# Stepper-Driver.net
KiCad netlist of a schematic drawn in Altium Designer
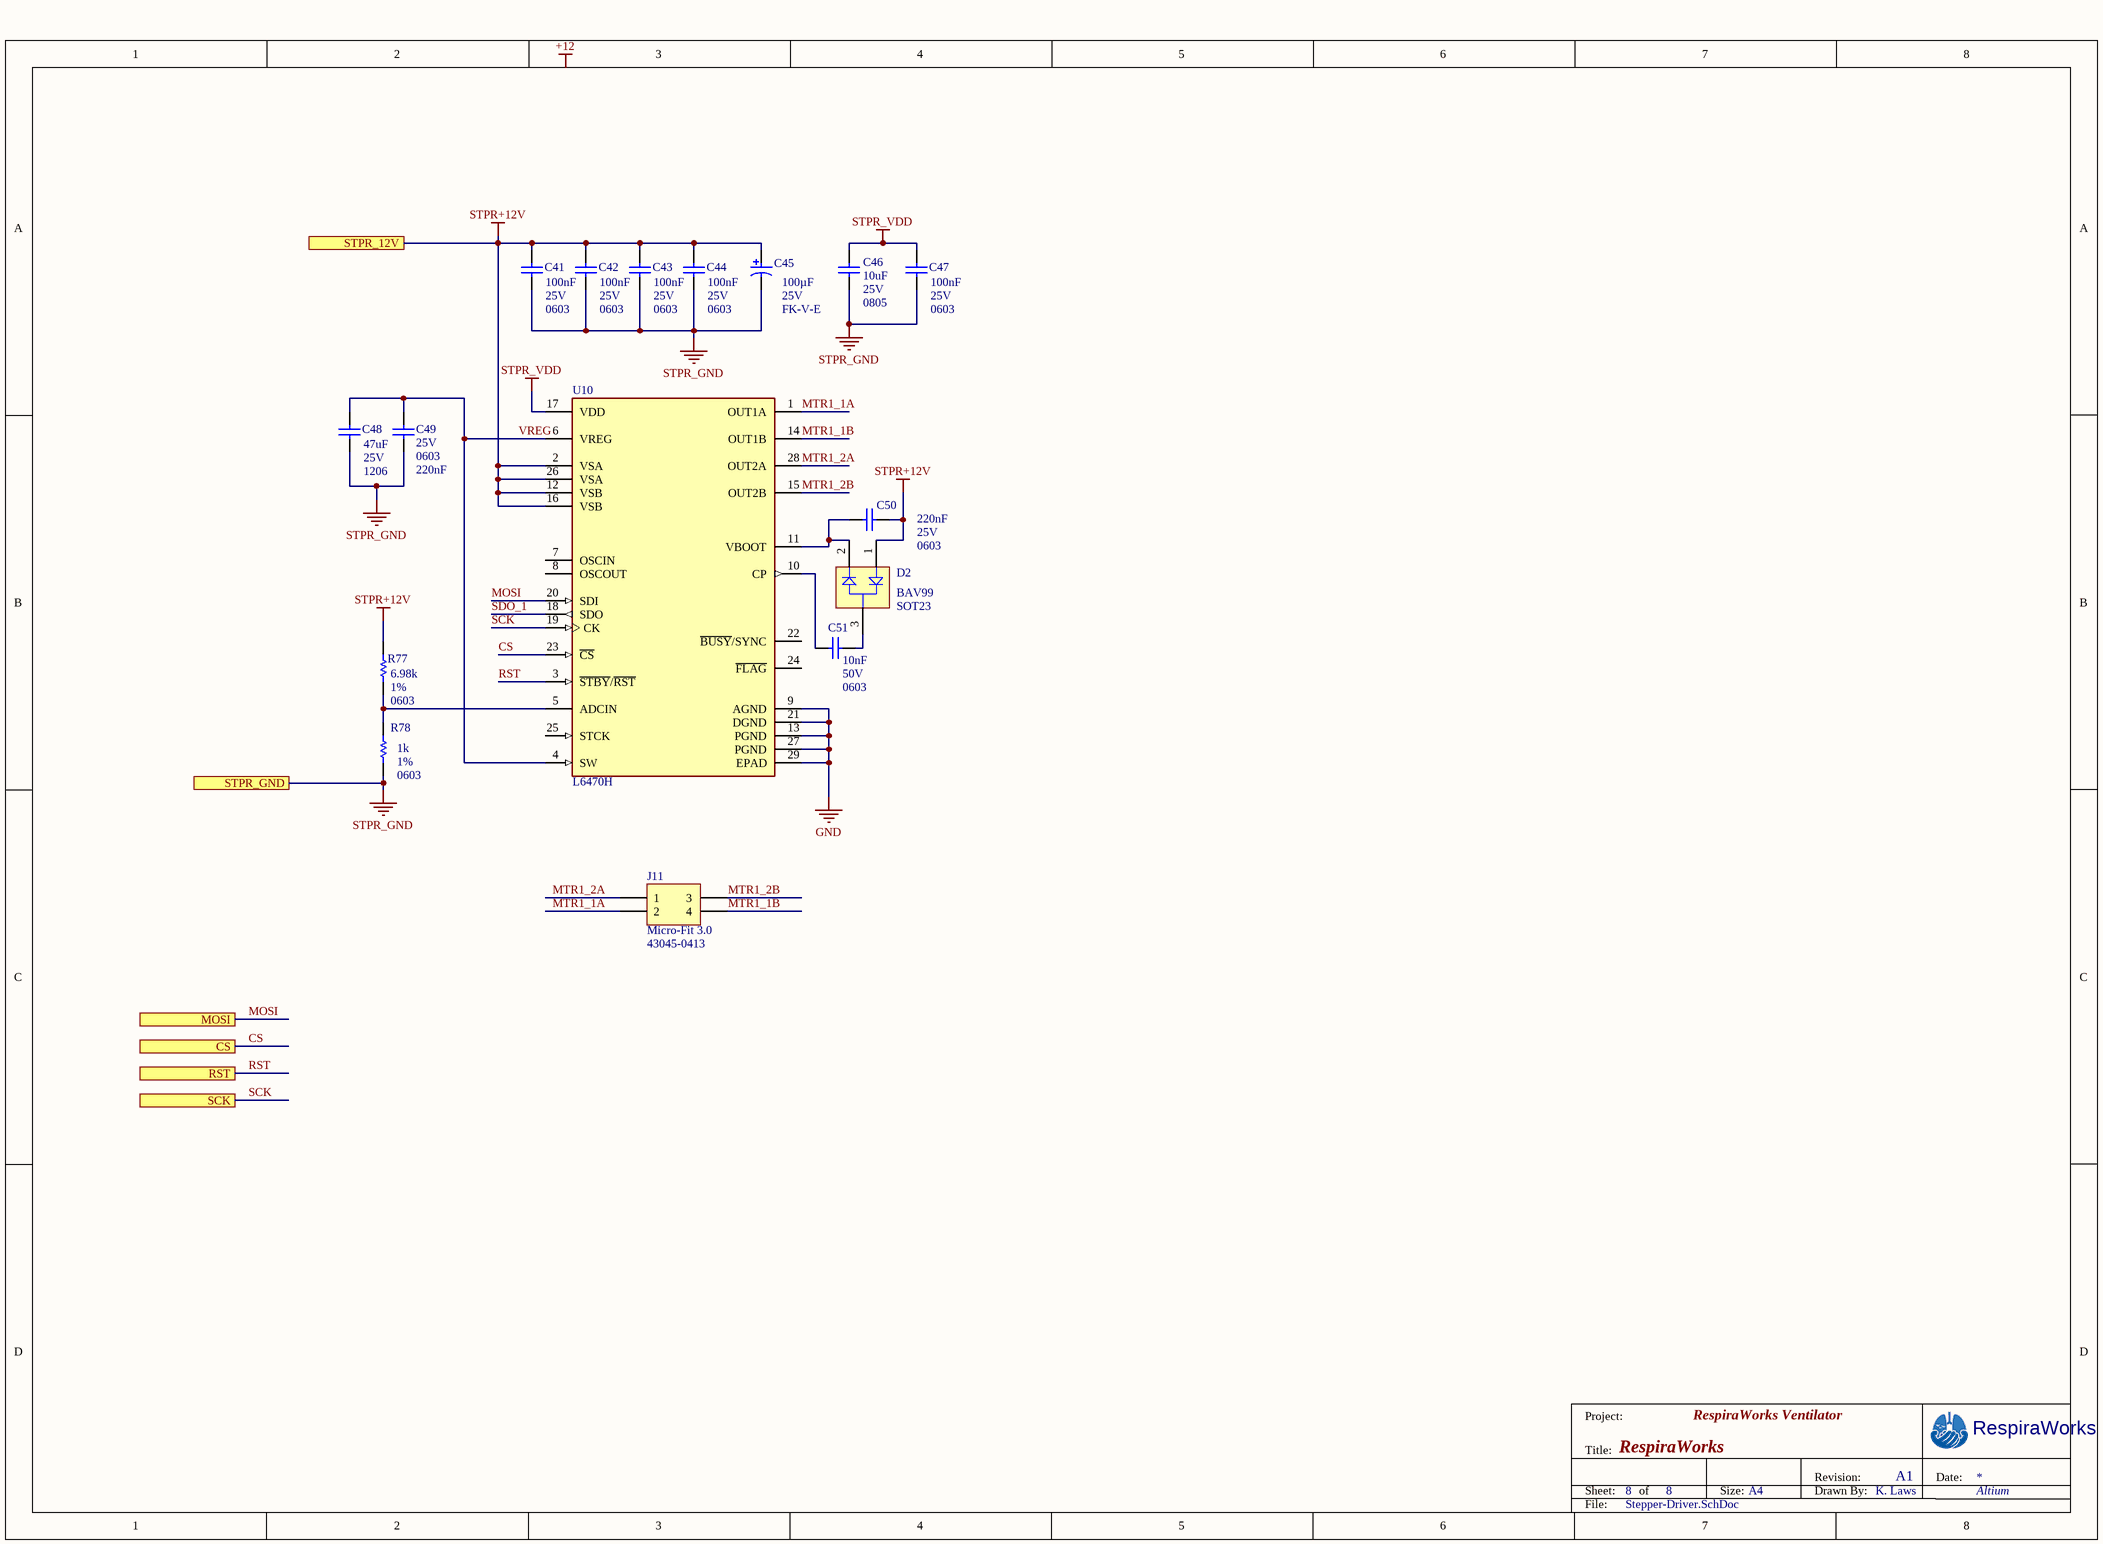
[diagram p0: Stepper-Driver.SchDoc]

(export (version "E")
  (design (tool "Eeschema 10.0.6"))
  (components
    (comp (ref "C41")
      (value "C0603C104Z3VACTU")
      (footprint "pcbreath:CAPC1608X87X35NL15T15")
      (fields
        (field (name "MANUFACTURER") "Kemet")
        (field (name "CASE/PACKAGE") "0603")
        (field (name "CAPACITANCE") "100nF")
        (field (name "TOLERANCE") "80%")
        (field (name "VOLTAGE RATING") "25V")
        (field (name "VOLTAGE") "25V")
      )
      (libsource (lib "pcbreath") (part "Capacitor 220nF"))
    )
    (comp (ref "C42")
      (value "C0603C104Z3VACTU")
      (footprint "pcbreath:CAPC1608X87X35NL15T15")
      (fields
        (field (name "MANUFACTURER") "Kemet")
        (field (name "CASE/PACKAGE") "0603")
        (field (name "CAPACITANCE") "100nF")
        (field (name "TOLERANCE") "80%")
        (field (name "VOLTAGE RATING") "25V")
        (field (name "VOLTAGE") "25V")
      )
      (libsource (lib "pcbreath") (part "Capacitor 220nF"))
    )
    (comp (ref "C43")
      (value "C0603C104Z3VACTU")
      (footprint "pcbreath:CAPC1608X87X35NL15T15")
      (fields
        (field (name "MANUFACTURER") "Kemet")
        (field (name "CASE/PACKAGE") "0603")
        (field (name "CAPACITANCE") "100nF")
        (field (name "TOLERANCE") "80%")
        (field (name "VOLTAGE RATING") "25V")
        (field (name "VOLTAGE") "25V")
      )
      (libsource (lib "pcbreath") (part "Capacitor 220nF"))
    )
    (comp (ref "C44")
      (value "C0603C104Z3VACTU")
      (footprint "pcbreath:CAPC1608X87X35NL15T15")
      (fields
        (field (name "MANUFACTURER") "Kemet")
        (field (name "CASE/PACKAGE") "0603")
        (field (name "CAPACITANCE") "100nF")
        (field (name "TOLERANCE") "80%")
        (field (name "VOLTAGE RATING") "25V")
        (field (name "VOLTAGE") "25V")
      )
      (libsource (lib "pcbreath") (part "Capacitor 220nF"))
    )
    (comp (ref "C45")
      (value "EEEFK1E101P")
      (footprint "pcbreath:PNSC-FK-V-E_V")
      (fields
        (field (name "RATED VOLTAGE") "25V")
        (field (name "PACKAGE REFERENCE") "FK-V-E")
        (field (name "MANUFACTURER") "Panasonic")
        (field (name "CAPACITANCE") "100µF")
      )
      (libsource (lib "pcbreath") (part "Capacitor 100 uF"))
    )
    (comp (ref "C46")
      (value "Capacitor 10 uF")
      (footprint "pcbreath:CAPC2013X135X45LL10T25")
      (description "Generic capacitor 0805 pkg")
      (fields
        (field (name "TOLERANCE") "10%")
        (field (name "VOLTAGE") "25V")
        (field (name "VOLTAGE RATING") "25V")
        (field (name "CASE/PACKAGE") "0805")
        (field (name "CAPACITANCE") "10uF")
      )
      (libsource (lib "pcbreath") (part "Capacitor 10 uF"))
    )
    (comp (ref "C47")
      (value "C0603C104Z3VACTU")
      (footprint "pcbreath:CAPC1608X87X35NL15T15")
      (fields
        (field (name "MANUFACTURER") "Kemet")
        (field (name "CASE/PACKAGE") "0603")
        (field (name "CAPACITANCE") "100nF")
        (field (name "TOLERANCE") "80%")
        (field (name "VOLTAGE RATING") "25V")
        (field (name "VOLTAGE") "25V")
      )
      (libsource (lib "pcbreath") (part "Capacitor 220nF"))
    )
    (comp (ref "C48")
      (value "Capacitor 47uF")
      (footprint "pcbreath:FP-C3216-160-IPC_B")
      (fields
        (field (name "CASE/PACKAGE") "1206")
        (field (name "CAPACITANCE") "47uF")
        (field (name "TOLERANCE") "20%")
        (field (name "VOLTAGE RATING") "25V")
        (field (name "VOLTAGE") "25V")
      )
      (libsource (lib "pcbreath") (part "Capacitor 47uF"))
    )
    (comp (ref "C49")
      (value "Capacitor 220nF")
      (footprint "pcbreath:CAPC1608X87X35NL15T15")
      (description "Capacitor 220 nF 25 VDC PU=4000 ST, GRM188R71E224KA88D, Murata")
      (fields
        (field (name "TOLERANCE") "10%")
        (field (name "VOLTAGE") "50V")
        (field (name "VOLTAGE RATING (DC)") "25V")
        (field (name "CASE/PACKAGE") "0603")
        (field (name "CAPACITANCE") "220nF")
      )
      (libsource (lib "") (part "Capacitor 220nF_1"))
    )
    (comp (ref "C50")
      (value "Capacitor 220nF")
      (footprint "CAPC0603(1608)100_L")
      (description "Capacitor 220 nF 25 VDC PU=4000 ST, GRM188R71E224KA88D, Murata")
      (fields
        (field (name "TOLERANCE") "10%")
        (field (name "VOLTAGE") "50V")
        (field (name "VOLTAGE RATING (DC)") "25V")
        (field (name "CASE/PACKAGE") "0603")
        (field (name "CAPACITANCE") "220nF")
      )
      (libsource (lib "") (part "Capacitor 220nF_1"))
    )
    (comp (ref "C51")
      (value "Capacitor 10nF")
      (footprint "pcbreath:CAPC0603(1608)100_L")
      (description "Cap Ceramic 0.01uF 50V X7R 10% SMD 0603 125C Automotive T/R")
      (fields
        (field (name "TOLERANCE") "10%")
        (field (name "VOLTAGE") "50V")
        (field (name "VOLTAGE RATING (DC)") "50V")
        (field (name "CAPACITANCE") "10nF")
        (field (name "CASE/PACKAGE") "0603")
      )
      (libsource (lib "pcbreath") (part "Capacitor 10nF"))
    )
    (comp (ref "D2")
      (value "BAV99")
      (footprint "pcbreath:INF-SOT23_L")
      (description "Silicon Switching Diode, SOT23, Reel, Green")
      (fields (field (name "MANUFACTURER") "Infineon") (field (name "PACKAGEREFERENCE") "SOT23"))
      (libsource (lib "pcbreath") (part "Silicon Switching Diode"))
    )
    (comp (ref "J11")
      (value "Micro-Fit 3.0")
      (footprint "pcbreath:43045-0413")
      (description "Conn, Micro-Fit 3.0, PCB Male Pin, 2x2pos, Thru-hole")
      (fields (field (name "MANUFACTURER") "Molex") (field (name "MANUFACTURER P/N") "43045-0413"))
      (libsource (lib "pcbreath") (part "43045-0413"))
    )
    (comp (ref "R77")
      (value "Res 6.98k")
      (footprint "pcbreath:RESC1608X55X30NL15T15")
      (fields
        (field (name "TOLERANCE") "1%")
        (field (name "CASE/PACKAGE") "0603")
        (field (name "RESISTANCE") "6.98k")
      )
      (libsource (lib "pcbreath") (part "Res 6.98k"))
    )
    (comp (ref "R78")
      (value "Res 1.0k 0603")
      (footprint "pcbreath:RESC1608X55X30NL15T15")
      (description "Res Thick Film 0603 1K Ohm 1% 1/10W ±100ppm/°C Molded SMD Punched Carrier T/R")
      (fields
        (field (name "RESISTANCE") "1k")
        (field (name "TOLERANCE") "1%")
        (field (name "CASE/PACKAGE") "0603")
      )
      (libsource (lib "pcbreath") (part "Res 1.0k 0603"))
    )
    (comp (ref "U10")
      (value "L6470H")
      (footprint "FP-HTSSOP28-AM02392-IPC_B")
      (description "Microstepping Motor Driver 3.3V 28-Pin HTSSOP Tube")
      (libsource (lib "pcbreath") (part "L6470H"))
    )
  )
  (nets
    (net (code "2") (name "/CS") (class "Default")
      (node (ref "U10") (pin "23") (pinfunction "~{CS}_23") (pintype "input"))
    )
    (net (code "3") (name "/MOSI") (class "Default")
      (node (ref "U10") (pin "20") (pinfunction "SDI_20") (pintype "input"))
    )
    (net (code "4") (name "/MTR1_1A") (class "Default")
      (node (ref "J11") (pin "2") (pinfunction "2_2") (pintype "passive"))
      (node (ref "U10") (pin "1") (pinfunction "OUT1A_1") (pintype "power_in"))
    )
    (net (code "5") (name "/MTR1_1B") (class "Default")
      (node (ref "J11") (pin "4") (pinfunction "4_4") (pintype "passive"))
      (node (ref "U10") (pin "14") (pinfunction "OUT1B_14") (pintype "power_in"))
    )
    (net (code "6") (name "/MTR1_2A") (class "Default")
      (node (ref "J11") (pin "1") (pinfunction "1_1") (pintype "passive"))
      (node (ref "U10") (pin "28") (pinfunction "OUT2A_28") (pintype "power_in"))
    )
    (net (code "7") (name "/MTR1_2B") (class "Default")
      (node (ref "J11") (pin "3") (pinfunction "3_3") (pintype "passive"))
      (node (ref "U10") (pin "15") (pinfunction "OUT2B_15") (pintype "power_in"))
    )
    (net (code "8") (name "/RST") (class "Default")
      (node (ref "U10") (pin "3") (pinfunction "~{STBY}/~{RST}_3") (pintype "input"))
    )
    (net (code "9") (name "/SCK") (class "Default")
      (node (ref "U10") (pin "19") (pinfunction "CK_19") (pintype "input"))
    )
    (net (code "10") (name "/SDO_1") (class "Default")
      (node (ref "U10") (pin "18") (pinfunction "SDO_18") (pintype "output"))
    )
    (net (code "11") (name "/VREG") (class "Default")
      (node (ref "C48") (pin "2") (pinfunction "2_2") (pintype "passive"))
      (node (ref "C49") (pin "2") (pinfunction "2_2") (pintype "passive"))
      (node (ref "U10") (pin "4") (pinfunction "SW_4") (pintype "input"))
      (node (ref "U10") (pin "6") (pinfunction "VREG_6") (pintype "power_in"))
    )
    (net (code "12") (name "GND") (class "Default")
      (node (ref "U10") (pin "13") (pinfunction "PGND_13") (pintype "power_in"))
      (node (ref "U10") (pin "21") (pinfunction "DGND_21") (pintype "power_in"))
      (node (ref "U10") (pin "27") (pinfunction "PGND_27") (pintype "power_in"))
      (node (ref "U10") (pin "29") (pinfunction "EPAD_29") (pintype "power_in"))
      (node (ref "U10") (pin "9") (pinfunction "AGND_9") (pintype "power_in"))
    )
    (net (code "13") (name "Net-(D2-C)") (class "Default")
      (node (ref "C51") (pin "2") (pinfunction "2_2") (pintype "passive"))
      (node (ref "D2") (pin "3") (pinfunction "C_3") (pintype "passive"))
    )
    (net (code "14") (name "Net-(D2-K2)") (class "Default")
      (node (ref "C50") (pin "1") (pinfunction "1_1") (pintype "passive"))
      (node (ref "D2") (pin "2") (pinfunction "K2_2") (pintype "passive"))
      (node (ref "U10") (pin "11") (pinfunction "VBOOT_11") (pintype "passive"))
    )
    (net (code "15") (name "Net-(U10-ADCIN)") (class "Default")
      (node (ref "R77") (pin "1") (pinfunction "1_1") (pintype "passive"))
      (node (ref "R78") (pin "2") (pinfunction "2_2") (pintype "passive"))
      (node (ref "U10") (pin "5") (pinfunction "ADCIN_5") (pintype "passive"))
    )
    (net (code "16") (name "Net-(U10-CP)") (class "Default")
      (node (ref "C51") (pin "1") (pinfunction "1_1") (pintype "passive"))
      (node (ref "U10") (pin "10") (pinfunction "CP_10") (pintype "output"))
    )
    (net (code "17") (name "STPR+12V") (class "Default")
      (node (ref "C41") (pin "2") (pinfunction "2_2") (pintype "passive"))
      (node (ref "C42") (pin "2") (pinfunction "2_2") (pintype "passive"))
      (node (ref "C43") (pin "2") (pinfunction "2_2") (pintype "passive"))
      (node (ref "C44") (pin "2") (pinfunction "2_2") (pintype "passive"))
      (node (ref "C45") (pin "1") (pinfunction "1_1") (pintype "passive"))
      (node (ref "C50") (pin "2") (pinfunction "2_2") (pintype "passive"))
      (node (ref "D2") (pin "1") (pinfunction "A1_1") (pintype "passive"))
      (node (ref "R77") (pin "2") (pinfunction "2_2") (pintype "passive"))
      (node (ref "U10") (pin "12") (pinfunction "VSB_12") (pintype "power_in"))
      (node (ref "U10") (pin "16") (pinfunction "VSB_16") (pintype "power_in"))
      (node (ref "U10") (pin "2") (pinfunction "VSA_2") (pintype "power_in"))
      (node (ref "U10") (pin "26") (pinfunction "VSA_26") (pintype "power_in"))
    )
    (net (code "18") (name "STPR_GND") (class "Default")
      (node (ref "C41") (pin "1") (pinfunction "1_1") (pintype "passive"))
      (node (ref "C42") (pin "1") (pinfunction "1_1") (pintype "passive"))
      (node (ref "C43") (pin "1") (pinfunction "1_1") (pintype "passive"))
      (node (ref "C44") (pin "1") (pinfunction "1_1") (pintype "passive"))
      (node (ref "C45") (pin "2") (pinfunction "2_2") (pintype "passive"))
      (node (ref "C46") (pin "1") (pinfunction "1_1") (pintype "passive"))
      (node (ref "C47") (pin "1") (pinfunction "1_1") (pintype "passive"))
      (node (ref "C48") (pin "1") (pinfunction "1_1") (pintype "passive"))
      (node (ref "C49") (pin "1") (pinfunction "1_1") (pintype "passive"))
      (node (ref "R78") (pin "1") (pinfunction "1_1") (pintype "passive"))
    )
    (net (code "19") (name "STPR_VDD") (class "Default")
      (node (ref "C46") (pin "2") (pinfunction "2_2") (pintype "passive"))
      (node (ref "C47") (pin "2") (pinfunction "2_2") (pintype "passive"))
      (node (ref "U10") (pin "17") (pinfunction "VDD_17") (pintype "power_in"))
    )
    (net (code "20") (name "unconnected-(U10-OSCIN-Pad7)") (class "Default")
      (node (ref "U10") (pin "7") (pinfunction "OSCIN_7") (pintype "passive"))
    )
    (net (code "21") (name "unconnected-(U10-OSCOUT-Pad8)") (class "Default")
      (node (ref "U10") (pin "8") (pinfunction "OSCOUT_8") (pintype "passive"))
    )
    (net (code "22") (name "unconnected-(U10-STCK-Pad25)") (class "Default")
      (node (ref "U10") (pin "25") (pinfunction "STCK_25") (pintype "input"))
    )
    (net (code "23") (name "unconnected-(U10-~{BUSY}{slash}SYNC-Pad22)") (class "Default")
      (node (ref "U10") (pin "22") (pinfunction "~{BUSY}/SYNC_22") (pintype "open_collector"))
    )
    (net (code "24") (name "unconnected-(U10-~{FLAG}-Pad24)") (class "Default")
      (node (ref "U10") (pin "24") (pinfunction "~{FLAG}_24") (pintype "open_collector"))
    )
  )
)
